# Power_Distribution.net
KiCad netlist of a schematic drawn in EAGLE
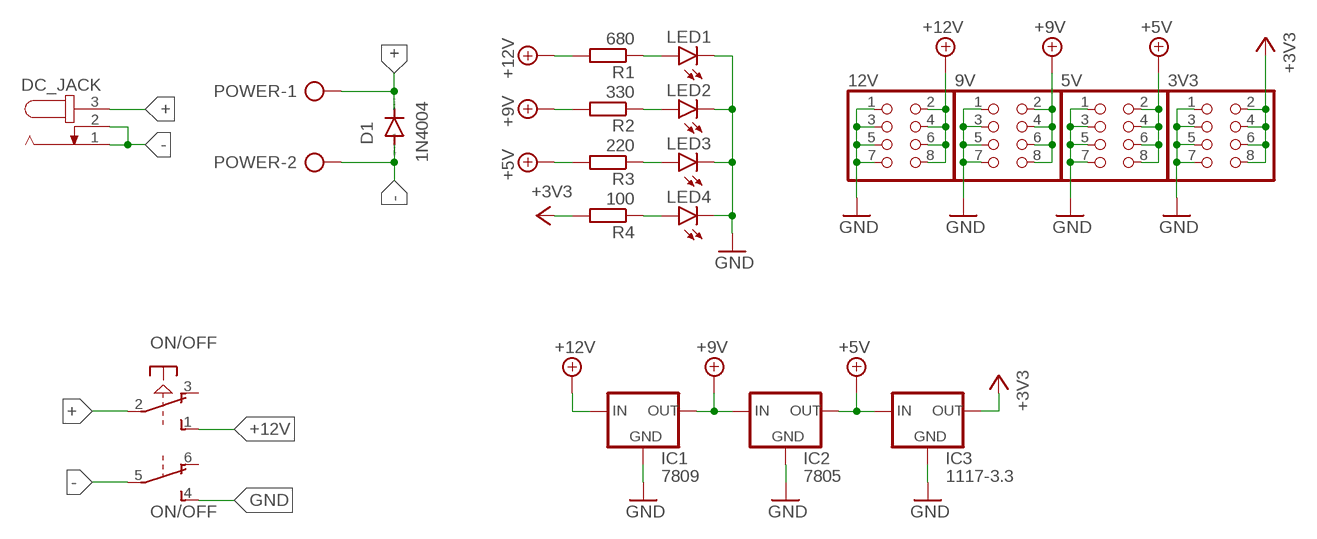
[diagram p0: schematic, sheet 1]

(export (version "E")
  (design (tool "Eeschema 10.0.6"))
  (components
    (comp (ref "3V3")
      (value "PINHD-2X4")
      (footprint "eagle-import:2X04")
      (libsource (lib "eagle-import") (part "PINHD-2X4"))
    )
    (comp (ref "5V")
      (value "PINHD-2X4")
      (footprint "eagle-import:2X04")
      (libsource (lib "eagle-import") (part "PINHD-2X4"))
    )
    (comp (ref "9V")
      (value "PINHD-2X4")
      (footprint "eagle-import:2X04")
      (libsource (lib "eagle-import") (part "PINHD-2X4"))
    )
    (comp (ref "12V")
      (value "PINHD-2X4")
      (footprint "eagle-import:2X04")
      (libsource (lib "eagle-import") (part "PINHD-2X4"))
    )
    (comp (ref "D1")
      (value "1N4004")
      (footprint "eagle-import:DO41-10")
      (libsource (lib "eagle-import") (part "1N4004"))
    )
    (comp (ref "DC_JACK")
      (value "JACK-PLUG0")
      (footprint "eagle-import:SPC4077")
      (libsource (lib "eagle-import") (part "JACK-PLUG0"))
    )
    (comp (ref "IC1")
      (value "7809")
      (footprint "eagle-import:78XXS")
      (libsource (lib "eagle-import") (part "78XXS"))
    )
    (comp (ref "IC2")
      (value "7805")
      (footprint "eagle-import:78XXS")
      (libsource (lib "eagle-import") (part "78XXS"))
    )
    (comp (ref "IC3")
      (value "1117-3.3")
      (footprint "eagle-import:78XXS")
      (libsource (lib "eagle-import") (part "78XXS"))
    )
    (comp (ref "LED1")
      (value "LED5MM")
      (footprint "eagle-import:LED5MM")
      (libsource (lib "eagle-import") (part "LED5MM"))
    )
    (comp (ref "LED2")
      (value "LED5MM")
      (footprint "eagle-import:LED5MM")
      (libsource (lib "eagle-import") (part "LED5MM"))
    )
    (comp (ref "LED3")
      (value "LED5MM")
      (footprint "eagle-import:LED5MM")
      (libsource (lib "eagle-import") (part "LED5MM"))
    )
    (comp (ref "LED4")
      (value "LED5MM")
      (footprint "eagle-import:LED5MM")
      (libsource (lib "eagle-import") (part "LED5MM"))
    )
    (comp (ref "ON/OFF")
      (value "PVA2R")
      (footprint "eagle-import:PVA2R")
      (libsource (lib "eagle-import") (part "PVA2R"))
    )
    (comp (ref "POWER")
      (value "AK500/2-H")
      (footprint "eagle-import:AK500_2-H")
      (libsource (lib "eagle-import") (part "AK500/2-H"))
    )
    (comp (ref "R1")
      (value "680")
      (footprint "eagle-import:0207_10")
      (libsource (lib "eagle-import") (part "R-EU_0207/10"))
    )
    (comp (ref "R2")
      (value "330")
      (footprint "eagle-import:0207_10")
      (libsource (lib "eagle-import") (part "R-EU_0207/10"))
    )
    (comp (ref "R3")
      (value "220")
      (footprint "eagle-import:0207_10")
      (libsource (lib "eagle-import") (part "R-EU_0207/10"))
    )
    (comp (ref "R4")
      (value "100")
      (footprint "eagle-import:0207_10")
      (libsource (lib "eagle-import") (part "R-EU_0207/10"))
    )
  )
  (nets
    (net (code "1") (name "+") (class "Default")
      (node (ref "D1") (pin "C") (pinfunction "C_C") (pintype "passive"))
      (node (ref "DC_JACK") (pin "3") (pinfunction "3_3") (pintype "passive"))
      (node (ref "ON/OFF") (pin "2") (pinfunction "P_2") (pintype "passive"))
      (node (ref "POWER") (pin "1") (pinfunction "KL_1") (pintype "passive"))
    )
    (net (code "2") (name "+3V3") (class "Default")
      (node (ref "3V3") (pin "2") (pinfunction "2_2") (pintype "passive"))
      (node (ref "3V3") (pin "4") (pinfunction "4_4") (pintype "passive"))
      (node (ref "3V3") (pin "6") (pinfunction "6_6") (pintype "passive"))
      (node (ref "3V3") (pin "8") (pinfunction "8_8") (pintype "passive"))
      (node (ref "IC3") (pin "OUT") (pinfunction "OUT_OUT") (pintype "passive"))
      (node (ref "R4") (pin "2") (pinfunction "2_2") (pintype "passive"))
    )
    (net (code "3") (name "+5V") (class "Default")
      (node (ref "5V") (pin "2") (pinfunction "2_2") (pintype "passive"))
      (node (ref "5V") (pin "4") (pinfunction "4_4") (pintype "passive"))
      (node (ref "5V") (pin "6") (pinfunction "6_6") (pintype "passive"))
      (node (ref "5V") (pin "8") (pinfunction "8_8") (pintype "passive"))
      (node (ref "IC2") (pin "OUT") (pinfunction "OUT_OUT") (pintype "passive"))
      (node (ref "IC3") (pin "IN") (pinfunction "IN_IN") (pintype "input"))
      (node (ref "R3") (pin "2") (pinfunction "2_2") (pintype "passive"))
    )
    (net (code "4") (name "+9V") (class "Default")
      (node (ref "9V") (pin "2") (pinfunction "2_2") (pintype "passive"))
      (node (ref "9V") (pin "4") (pinfunction "4_4") (pintype "passive"))
      (node (ref "9V") (pin "6") (pinfunction "6_6") (pintype "passive"))
      (node (ref "9V") (pin "8") (pinfunction "8_8") (pintype "passive"))
      (node (ref "IC1") (pin "OUT") (pinfunction "OUT_OUT") (pintype "passive"))
      (node (ref "IC2") (pin "IN") (pinfunction "IN_IN") (pintype "input"))
      (node (ref "R2") (pin "2") (pinfunction "2_2") (pintype "passive"))
    )
    (net (code "5") (name "+12V") (class "Default")
      (node (ref "12V") (pin "2") (pinfunction "2_2") (pintype "passive"))
      (node (ref "12V") (pin "4") (pinfunction "4_4") (pintype "passive"))
      (node (ref "12V") (pin "6") (pinfunction "6_6") (pintype "passive"))
      (node (ref "12V") (pin "8") (pinfunction "8_8") (pintype "passive"))
      (node (ref "IC1") (pin "IN") (pinfunction "IN_IN") (pintype "input"))
      (node (ref "ON/OFF") (pin "1") (pinfunction "S_1") (pintype "passive"))
      (node (ref "R1") (pin "2") (pinfunction "2_2") (pintype "passive"))
    )
    (net (code "6") (name "-") (class "Default")
      (node (ref "D1") (pin "A") (pinfunction "A_A") (pintype "passive"))
      (node (ref "DC_JACK") (pin "1") (pinfunction "1_1") (pintype "passive"))
      (node (ref "DC_JACK") (pin "2") (pinfunction "2_2") (pintype "passive"))
      (node (ref "ON/OFF") (pin "5") (pinfunction "P_5") (pintype "passive"))
      (node (ref "POWER") (pin "2") (pinfunction "KL_2") (pintype "passive"))
    )
    (net (code "7") (name "GND") (class "Default")
      (node (ref "12V") (pin "1") (pinfunction "1_1") (pintype "passive"))
      (node (ref "12V") (pin "3") (pinfunction "3_3") (pintype "passive"))
      (node (ref "12V") (pin "5") (pinfunction "5_5") (pintype "passive"))
      (node (ref "12V") (pin "7") (pinfunction "7_7") (pintype "passive"))
      (node (ref "3V3") (pin "1") (pinfunction "1_1") (pintype "passive"))
      (node (ref "3V3") (pin "3") (pinfunction "3_3") (pintype "passive"))
      (node (ref "3V3") (pin "5") (pinfunction "5_5") (pintype "passive"))
      (node (ref "3V3") (pin "7") (pinfunction "7_7") (pintype "passive"))
      (node (ref "5V") (pin "1") (pinfunction "1_1") (pintype "passive"))
      (node (ref "5V") (pin "3") (pinfunction "3_3") (pintype "passive"))
      (node (ref "5V") (pin "5") (pinfunction "5_5") (pintype "passive"))
      (node (ref "5V") (pin "7") (pinfunction "7_7") (pintype "passive"))
      (node (ref "9V") (pin "1") (pinfunction "1_1") (pintype "passive"))
      (node (ref "9V") (pin "3") (pinfunction "3_3") (pintype "passive"))
      (node (ref "9V") (pin "5") (pinfunction "5_5") (pintype "passive"))
      (node (ref "9V") (pin "7") (pinfunction "7_7") (pintype "passive"))
      (node (ref "IC1") (pin "GND") (pinfunction "GND_GND") (pintype "input"))
      (node (ref "IC2") (pin "GND") (pinfunction "GND_GND") (pintype "input"))
      (node (ref "IC3") (pin "GND") (pinfunction "GND_GND") (pintype "input"))
      (node (ref "LED1") (pin "K") (pinfunction "C_K") (pintype "passive"))
      (node (ref "LED2") (pin "K") (pinfunction "C_K") (pintype "passive"))
      (node (ref "LED3") (pin "K") (pinfunction "C_K") (pintype "passive"))
      (node (ref "LED4") (pin "K") (pinfunction "C_K") (pintype "passive"))
      (node (ref "ON/OFF") (pin "4") (pinfunction "S_4") (pintype "passive"))
    )
    (net (code "8") (name "Net-(LED1-PadA)") (class "Default")
      (node (ref "LED1") (pin "A") (pinfunction "A_A") (pintype "passive"))
      (node (ref "R1") (pin "1") (pinfunction "1_1") (pintype "passive"))
    )
    (net (code "9") (name "Net-(LED2-PadA)") (class "Default")
      (node (ref "LED2") (pin "A") (pinfunction "A_A") (pintype "passive"))
      (node (ref "R2") (pin "1") (pinfunction "1_1") (pintype "passive"))
    )
    (net (code "10") (name "Net-(LED3-PadA)") (class "Default")
      (node (ref "LED3") (pin "A") (pinfunction "A_A") (pintype "passive"))
      (node (ref "R3") (pin "1") (pinfunction "1_1") (pintype "passive"))
    )
    (net (code "11") (name "Net-(LED4-PadA)") (class "Default")
      (node (ref "LED4") (pin "A") (pinfunction "A_A") (pintype "passive"))
      (node (ref "R4") (pin "1") (pinfunction "1_1") (pintype "passive"))
    )
    (net (code "12") (name "unconnected-(ON/OFFA-O-Pad3)") (class "Default")
      (node (ref "ON/OFF") (pin "3") (pinfunction "O_3") (pintype "passive"))
    )
    (net (code "13") (name "unconnected-(ON/OFFB-O-Pad6)") (class "Default")
      (node (ref "ON/OFF") (pin "6") (pinfunction "O_6") (pintype "passive"))
    )
  )
)
